# robotpin.net
KiCad netlist of a schematic drawn in EAGLE
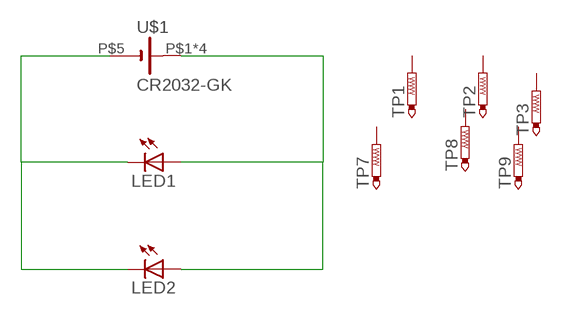
[diagram p0: schematic, sheet 1]

(export (version "E")
  (design (tool "Eeschema 10.0.6"))
  (components
    (comp (ref "LED1")
      (value "LED5MM")
      (footprint "eagle-import:LED5MM")
      (libsource (lib "eagle-import") (part "LED5MM"))
    )
    (comp (ref "LED2")
      (value "LED5MM")
      (footprint "eagle-import:LED5MM")
      (libsource (lib "eagle-import") (part "LED5MM"))
    )
    (comp (ref "TP1")
      (value "PTR1TP12R")
      (footprint "eagle-import:TP12R")
      (libsource (lib "eagle-import") (part "PTR1TP12R"))
    )
    (comp (ref "TP2")
      (value "PTR1TP12R")
      (footprint "eagle-import:TP12R")
      (libsource (lib "eagle-import") (part "PTR1TP12R"))
    )
    (comp (ref "TP3")
      (value "PTR1TP12R")
      (footprint "eagle-import:TP12R")
      (libsource (lib "eagle-import") (part "PTR1TP12R"))
    )
    (comp (ref "TP7")
      (value "PTR1TP12R")
      (footprint "eagle-import:TP12R")
      (libsource (lib "eagle-import") (part "PTR1TP12R"))
    )
    (comp (ref "TP8")
      (value "PTR1TP12R")
      (footprint "eagle-import:TP12R")
      (libsource (lib "eagle-import") (part "PTR1TP12R"))
    )
    (comp (ref "TP9")
      (value "PTR1TP12R")
      (footprint "eagle-import:TP12R")
      (libsource (lib "eagle-import") (part "PTR1TP12R"))
    )
    (comp (ref "U$1")
      (value "CR2032-GK")
      (footprint "eagle-import:BAT-HLD-001-THM")
      (libsource (lib "eagle-import") (part "CR2032-GK"))
    )
  )
  (nets
    (net (code "1") (name "Net-(LED1-C)") (class "Default")
      (node (ref "LED1") (pin "K") (pinfunction "C_K") (pintype "passive"))
      (node (ref "LED2") (pin "K") (pinfunction "C_K") (pintype "passive"))
      (node (ref "U$1") (pin "P$5") (pinfunction "-_P$5") (pintype "passive"))
    )
    (net (code "2") (name "Net-(LED1-PadA)") (class "Default")
      (node (ref "LED1") (pin "A") (pinfunction "A_A") (pintype "passive"))
      (node (ref "LED2") (pin "A") (pinfunction "A_A") (pintype "passive"))
      (node (ref "U$1") (pin "P$1") (pinfunction "+_P$1") (pintype "passive"))
      (node (ref "U$1") (pin "P$2") (pinfunction "+_P$2") (pintype "passive"))
      (node (ref "U$1") (pin "P$3") (pinfunction "+_P$3") (pintype "passive"))
      (node (ref "U$1") (pin "P$4") (pinfunction "+_P$4") (pintype "passive"))
    )
    (net (code "3") (name "unconnected-(TP1-PadTP)") (class "Default")
      (node (ref "TP1") (pin "TP") (pinfunction "TP_TP") (pintype "input"))
    )
    (net (code "4") (name "unconnected-(TP2-PadTP)") (class "Default")
      (node (ref "TP2") (pin "TP") (pinfunction "TP_TP") (pintype "input"))
    )
    (net (code "5") (name "unconnected-(TP3-PadTP)") (class "Default")
      (node (ref "TP3") (pin "TP") (pinfunction "TP_TP") (pintype "input"))
    )
    (net (code "6") (name "unconnected-(TP7-PadTP)") (class "Default")
      (node (ref "TP7") (pin "TP") (pinfunction "TP_TP") (pintype "input"))
    )
    (net (code "7") (name "unconnected-(TP8-PadTP)") (class "Default")
      (node (ref "TP8") (pin "TP") (pinfunction "TP_TP") (pintype "input"))
    )
    (net (code "8") (name "unconnected-(TP9-PadTP)") (class "Default")
      (node (ref "TP9") (pin "TP") (pinfunction "TP_TP") (pintype "input"))
    )
  )
)
